# fra_500k_4M.net
KiCad netlist of a schematic drawn in EAGLE
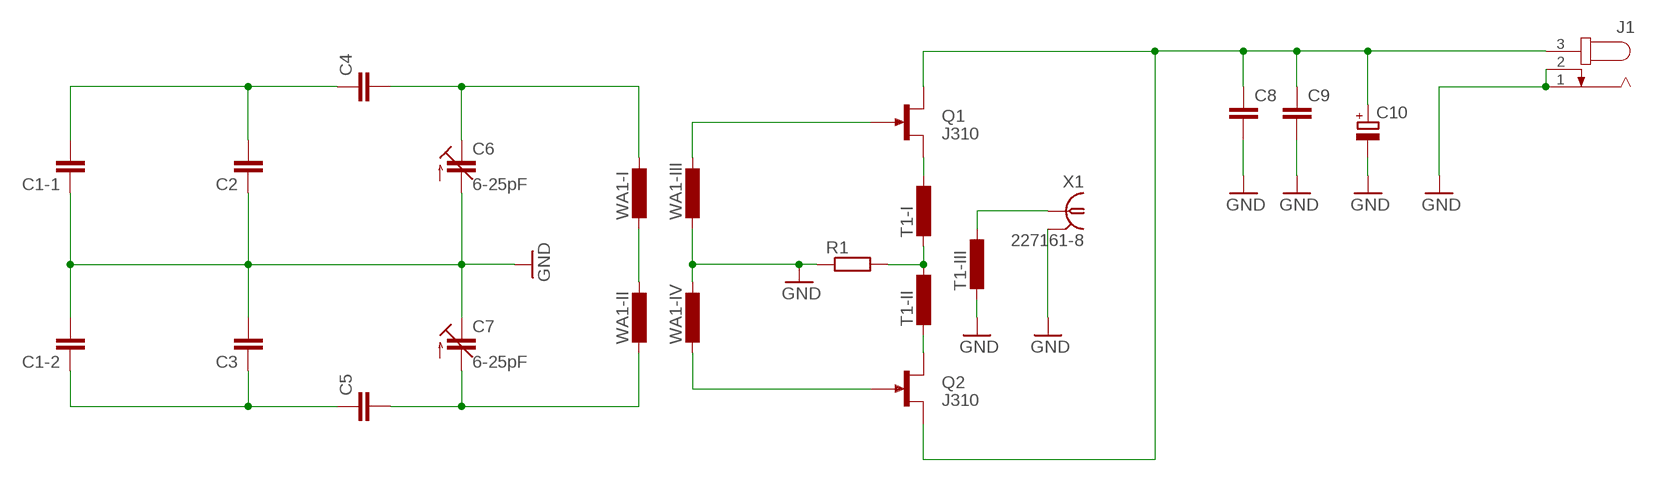
[diagram p0: schematic, sheet 1]

(export (version "E")
  (design (tool "Eeschema 10.0.6"))
  (components
    (comp (ref "C1-1")
      (value "C-EU075-032X103")
      (footprint "eagle-import:C075-032X103")
      (libsource (lib "eagle-import") (part "C-EU075-032X103"))
    )
    (comp (ref "C1-2")
      (value "C-EU075-032X103")
      (footprint "eagle-import:C075-032X103")
      (libsource (lib "eagle-import") (part "C-EU075-032X103"))
    )
    (comp (ref "C2")
      (value "C-EUC1210")
      (footprint "eagle-import:C1210")
      (libsource (lib "eagle-import") (part "C-EUC1210"))
    )
    (comp (ref "C3")
      (value "C-EUC1210")
      (footprint "eagle-import:C1210")
      (libsource (lib "eagle-import") (part "C-EUC1210"))
    )
    (comp (ref "C4")
      (value "C-EUC1210")
      (footprint "eagle-import:C1210")
      (libsource (lib "eagle-import") (part "C-EUC1210"))
    )
    (comp (ref "C5")
      (value "C-EUC1210")
      (footprint "eagle-import:C1210")
      (libsource (lib "eagle-import") (part "C-EUC1210"))
    )
    (comp (ref "C6")
      (value "6-25pF")
      (footprint "eagle-import:CTRIM3050.504")
      (libsource (lib "eagle-import") (part "C-TRIMM3050.504"))
    )
    (comp (ref "C7")
      (value "6-25pF")
      (footprint "eagle-import:CTRIM3050.504")
      (libsource (lib "eagle-import") (part "C-TRIMM3050.504"))
    )
    (comp (ref "C8")
      (value "C-EUC1206")
      (footprint "eagle-import:C1206")
      (libsource (lib "eagle-import") (part "C-EUC1206"))
    )
    (comp (ref "C9")
      (value "C-EUC1206")
      (footprint "eagle-import:C1206")
      (libsource (lib "eagle-import") (part "C-EUC1206"))
    )
    (comp (ref "C10")
      (value "CPOL-EUSMCC")
      (footprint "eagle-import:SMC_C")
      (libsource (lib "eagle-import") (part "CPOL-EUSMCC"))
    )
    (comp (ref "J1")
      (value "JACK-PLUG0")
      (footprint "eagle-import:SPC4077")
      (libsource (lib "eagle-import") (part "JACK-PLUG0"))
    )
    (comp (ref "Q1")
      (value "J310")
      (footprint "eagle-import:TO92R")
      (libsource (lib "eagle-import") (part "J310"))
    )
    (comp (ref "Q2")
      (value "J310")
      (footprint "eagle-import:TO92R")
      (libsource (lib "eagle-import") (part "J310"))
    )
    (comp (ref "R1")
      (value "R-EU_M1206")
      (footprint "eagle-import:M1206")
      (libsource (lib "eagle-import") (part "R-EU_M1206"))
    )
    (comp (ref "T1-I")
      (value "L-EU0204/7")
      (footprint "eagle-import:0204_7")
      (libsource (lib "eagle-import") (part "L-EU0204/7"))
    )
    (comp (ref "T1-II")
      (value "L-EU0204/7")
      (footprint "eagle-import:0204_7")
      (libsource (lib "eagle-import") (part "L-EU0204/7"))
    )
    (comp (ref "T1-III")
      (value "L-EU0204/7")
      (footprint "eagle-import:0204_7")
      (libsource (lib "eagle-import") (part "L-EU0204/7"))
    )
    (comp (ref "WA1-I")
      (value "L-EU0204/7")
      (footprint "eagle-import:0204_7")
      (libsource (lib "eagle-import") (part "L-EU0204/7"))
    )
    (comp (ref "WA1-II")
      (value "L-EU0204/7")
      (footprint "eagle-import:0204_7")
      (libsource (lib "eagle-import") (part "L-EU0204/7"))
    )
    (comp (ref "WA1-III")
      (value "L-EU0204/7")
      (footprint "eagle-import:0204_7")
      (libsource (lib "eagle-import") (part "L-EU0204/7"))
    )
    (comp (ref "WA1-IV")
      (value "L-EU0204/7")
      (footprint "eagle-import:0204_7")
      (libsource (lib "eagle-import") (part "L-EU0204/7"))
    )
    (comp (ref "X1")
      (value "227161-8")
      (footprint "eagle-import:AMP_227161")
      (libsource (lib "eagle-import") (part "?227161-8"))
    )
  )
  (nets
    (net (code "1") (name "GND") (class "Default")
      (node (ref "C1-1") (pin "1") (pinfunction "1_1") (pintype "passive"))
      (node (ref "C1-2") (pin "2") (pinfunction "2_2") (pintype "passive"))
      (node (ref "C10") (pin "-") (pinfunction "-_-") (pintype "passive"))
      (node (ref "C2") (pin "1") (pinfunction "1_1") (pintype "passive"))
      (node (ref "C3") (pin "2") (pinfunction "2_2") (pintype "passive"))
      (node (ref "C6") (pin "2") (pinfunction "A_2") (pintype "passive"))
      (node (ref "C7") (pin "1") (pinfunction "E_1") (pintype "passive"))
      (node (ref "C8") (pin "2") (pinfunction "2_2") (pintype "passive"))
      (node (ref "C9") (pin "2") (pinfunction "2_2") (pintype "passive"))
      (node (ref "J1") (pin "1") (pinfunction "1_1") (pintype "passive"))
      (node (ref "J1") (pin "2") (pinfunction "2_2") (pintype "passive"))
      (node (ref "R1") (pin "1") (pinfunction "1_1") (pintype "passive"))
      (node (ref "T1-III") (pin "2") (pinfunction "2_2") (pintype "passive"))
      (node (ref "WA1-III") (pin "2") (pinfunction "2_2") (pintype "passive"))
      (node (ref "WA1-IV") (pin "1") (pinfunction "1_1") (pintype "passive"))
      (node (ref "X1") (pin "2") (pinfunction "2_2") (pintype "passive"))
    )
    (net (code "2") (name "Net-(C1-1-Pad2)") (class "Default")
      (node (ref "C1-1") (pin "2") (pinfunction "2_2") (pintype "passive"))
      (node (ref "C2") (pin "2") (pinfunction "2_2") (pintype "passive"))
      (node (ref "C4") (pin "1") (pinfunction "1_1") (pintype "passive"))
    )
    (net (code "3") (name "Net-(C1-2-Pad1)") (class "Default")
      (node (ref "C1-2") (pin "1") (pinfunction "1_1") (pintype "passive"))
      (node (ref "C3") (pin "1") (pinfunction "1_1") (pintype "passive"))
      (node (ref "C5") (pin "1") (pinfunction "1_1") (pintype "passive"))
    )
    (net (code "4") (name "Net-(C6-E)") (class "Default")
      (node (ref "C4") (pin "2") (pinfunction "2_2") (pintype "passive"))
      (node (ref "C6") (pin "1") (pinfunction "E_1") (pintype "passive"))
      (node (ref "WA1-I") (pin "1") (pinfunction "1_1") (pintype "passive"))
    )
    (net (code "5") (name "Net-(C7-A)") (class "Default")
      (node (ref "C5") (pin "2") (pinfunction "2_2") (pintype "passive"))
      (node (ref "C7") (pin "2") (pinfunction "A_2") (pintype "passive"))
      (node (ref "WA1-II") (pin "2") (pinfunction "2_2") (pintype "passive"))
    )
    (net (code "6") (name "Net-(C10-Pad+)") (class "Default")
      (node (ref "C10") (pin "+") (pinfunction "+_+") (pintype "passive"))
      (node (ref "C8") (pin "1") (pinfunction "1_1") (pintype "passive"))
      (node (ref "C9") (pin "1") (pinfunction "1_1") (pintype "passive"))
      (node (ref "J1") (pin "3") (pinfunction "3_3") (pintype "passive"))
      (node (ref "Q1") (pin "D") (pinfunction "D_D") (pintype "passive"))
      (node (ref "Q2") (pin "S") (pinfunction "S_S") (pintype "passive"))
    )
    (net (code "7") (name "Net-(Q1-PadG)") (class "Default")
      (node (ref "Q1") (pin "G") (pinfunction "G_G") (pintype "passive"))
      (node (ref "WA1-III") (pin "1") (pinfunction "1_1") (pintype "passive"))
    )
    (net (code "8") (name "Net-(Q1-PadS)") (class "Default")
      (node (ref "Q1") (pin "S") (pinfunction "S_S") (pintype "passive"))
      (node (ref "T1-I") (pin "1") (pinfunction "1_1") (pintype "passive"))
    )
    (net (code "9") (name "Net-(Q2-PadD)") (class "Default")
      (node (ref "Q2") (pin "D") (pinfunction "D_D") (pintype "passive"))
      (node (ref "T1-II") (pin "2") (pinfunction "2_2") (pintype "passive"))
    )
    (net (code "10") (name "Net-(Q2-PadG)") (class "Default")
      (node (ref "Q2") (pin "G") (pinfunction "G_G") (pintype "passive"))
      (node (ref "WA1-IV") (pin "2") (pinfunction "2_2") (pintype "passive"))
    )
    (net (code "11") (name "Net-(R1-Pad2)") (class "Default")
      (node (ref "R1") (pin "2") (pinfunction "2_2") (pintype "passive"))
      (node (ref "T1-I") (pin "2") (pinfunction "2_2") (pintype "passive"))
      (node (ref "T1-II") (pin "1") (pinfunction "1_1") (pintype "passive"))
    )
    (net (code "12") (name "Net-(T1-III-Pad1)") (class "Default")
      (node (ref "T1-III") (pin "1") (pinfunction "1_1") (pintype "passive"))
      (node (ref "X1") (pin "1") (pinfunction "1_1") (pintype "passive"))
    )
    (net (code "13") (name "Net-(WA1-I-Pad2)") (class "Default")
      (node (ref "WA1-I") (pin "2") (pinfunction "2_2") (pintype "passive"))
      (node (ref "WA1-II") (pin "1") (pinfunction "1_1") (pintype "passive"))
    )
  )
)
